# 2020-10-27_AD590_HIH-4031.net
KiCad netlist of a schematic drawn in EAGLE
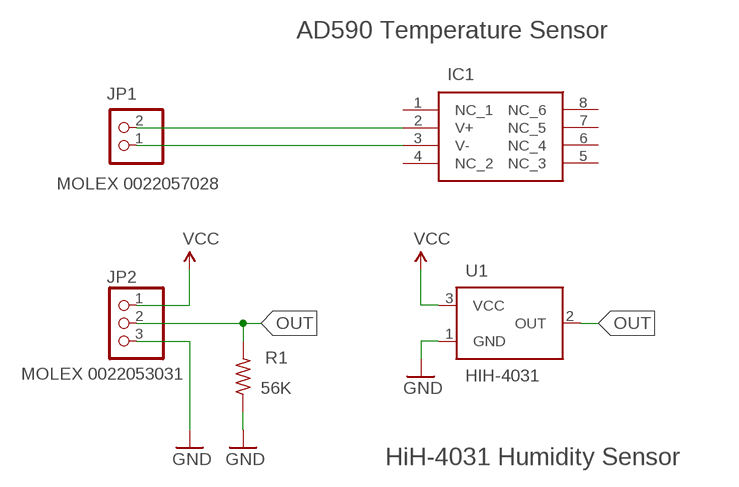
[diagram p0: schematic, sheet 1]

(export (version "E")
  (design (tool "Eeschema 10.0.6"))
  (components
    (comp (ref "IC1")
      (value "AD590JRZ")
      (footprint "eagle-import:SOIC127P600X175-8N")
      (fields (field (name "MOUSER_PART_NUMBER") "584-AD590JRZ") (field (name "RS_PART_NUMBER") "7096005P"))
      (libsource (lib "eagle-import") (part "AD590JRZ"))
    )
    (comp (ref "JP1")
      (value "MOLEX 0022057028")
      (footprint "eagle-import:MOLEX-7395-02-90DEG")
      (libsource (lib "eagle-import") (part "PINHD-1X2MOLEX-02-90DEG"))
    )
    (comp (ref "JP2")
      (value "MOLEX 0022053031")
      (footprint "eagle-import:MOLEX-7395-03-90DEG")
      (libsource (lib "eagle-import") (part "PINHD-1X3MOLEX-7395-03-RA"))
    )
    (comp (ref "R1")
      (value "56K")
      (footprint "eagle-import:R0805")
      (libsource (lib "eagle-import") (part "R-US_R0805"))
    )
    (comp (ref "U1")
      (value "HIH-4031")
      (footprint "eagle-import:HIH-4030")
      (libsource (lib "eagle-import") (part "HIH-4030"))
    )
  )
  (nets
    (net (code "1") (name "GND") (class "Default")
      (node (ref "JP2") (pin "3") (pinfunction "3_3") (pintype "passive"))
      (node (ref "R1") (pin "1") (pinfunction "1_1") (pintype "passive"))
      (node (ref "U1") (pin "1") (pinfunction "GND_1") (pintype "bidirectional"))
    )
    (net (code "2") (name "Net-(IC1-V+)") (class "Default")
      (node (ref "IC1") (pin "2") (pinfunction "V+_2") (pintype "bidirectional"))
      (node (ref "JP1") (pin "2") (pinfunction "2_2") (pintype "passive"))
    )
    (net (code "3") (name "Net-(IC1-V-)") (class "Default")
      (node (ref "IC1") (pin "3") (pinfunction "V-_3") (pintype "bidirectional"))
      (node (ref "JP1") (pin "1") (pinfunction "1_1") (pintype "passive"))
    )
    (net (code "4") (name "OUT") (class "Default")
      (node (ref "JP2") (pin "2") (pinfunction "2_2") (pintype "passive"))
      (node (ref "R1") (pin "2") (pinfunction "2_2") (pintype "passive"))
      (node (ref "U1") (pin "2") (pinfunction "OUT_2") (pintype "bidirectional"))
    )
    (net (code "5") (name "VCC") (class "Default")
      (node (ref "JP2") (pin "1") (pinfunction "1_1") (pintype "passive"))
      (node (ref "U1") (pin "3") (pinfunction "VCC_3") (pintype "bidirectional"))
    )
    (net (code "6") (name "unconnected-(IC1-NC_1-Pad1)") (class "Default")
      (node (ref "IC1") (pin "1") (pinfunction "NC_1_1") (pintype "bidirectional"))
    )
    (net (code "7") (name "unconnected-(IC1-NC_2-Pad4)") (class "Default")
      (node (ref "IC1") (pin "4") (pinfunction "NC_2_4") (pintype "bidirectional"))
    )
    (net (code "8") (name "unconnected-(IC1-NC_3-Pad5)") (class "Default")
      (node (ref "IC1") (pin "5") (pinfunction "NC_3_5") (pintype "bidirectional"))
    )
    (net (code "9") (name "unconnected-(IC1-NC_4-Pad6)") (class "Default")
      (node (ref "IC1") (pin "6") (pinfunction "NC_4_6") (pintype "bidirectional"))
    )
    (net (code "10") (name "unconnected-(IC1-NC_5-Pad7)") (class "Default")
      (node (ref "IC1") (pin "7") (pinfunction "NC_5_7") (pintype "bidirectional"))
    )
    (net (code "11") (name "unconnected-(IC1-NC_6-Pad8)") (class "Default")
      (node (ref "IC1") (pin "8") (pinfunction "NC_6_8") (pintype "bidirectional"))
    )
  )
)
